# Inverter_v1p0.net
KiCad netlist of a schematic drawn in EAGLE
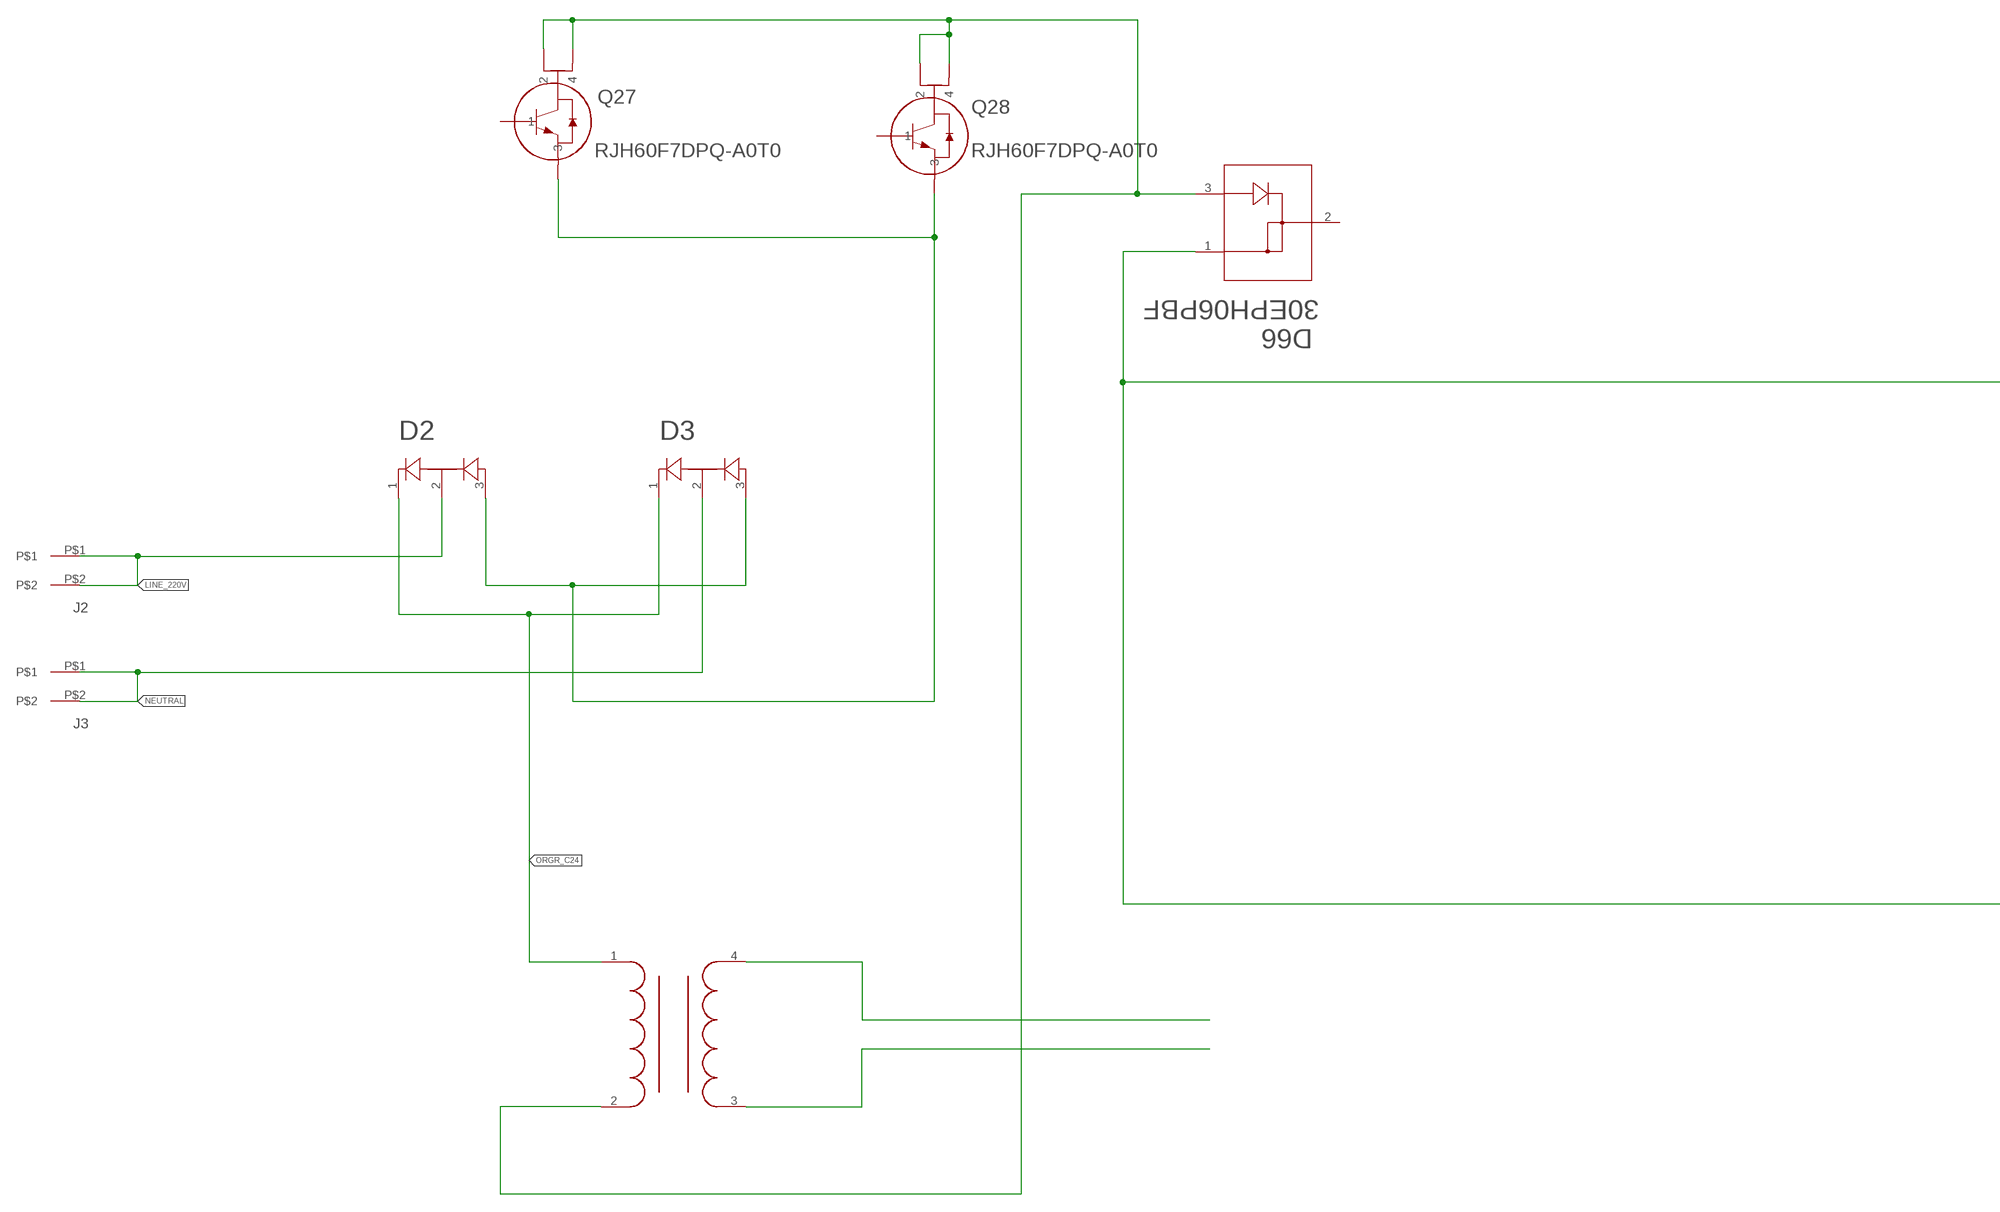
[diagram p0: schematic, sheet 1, part 1 of 2]
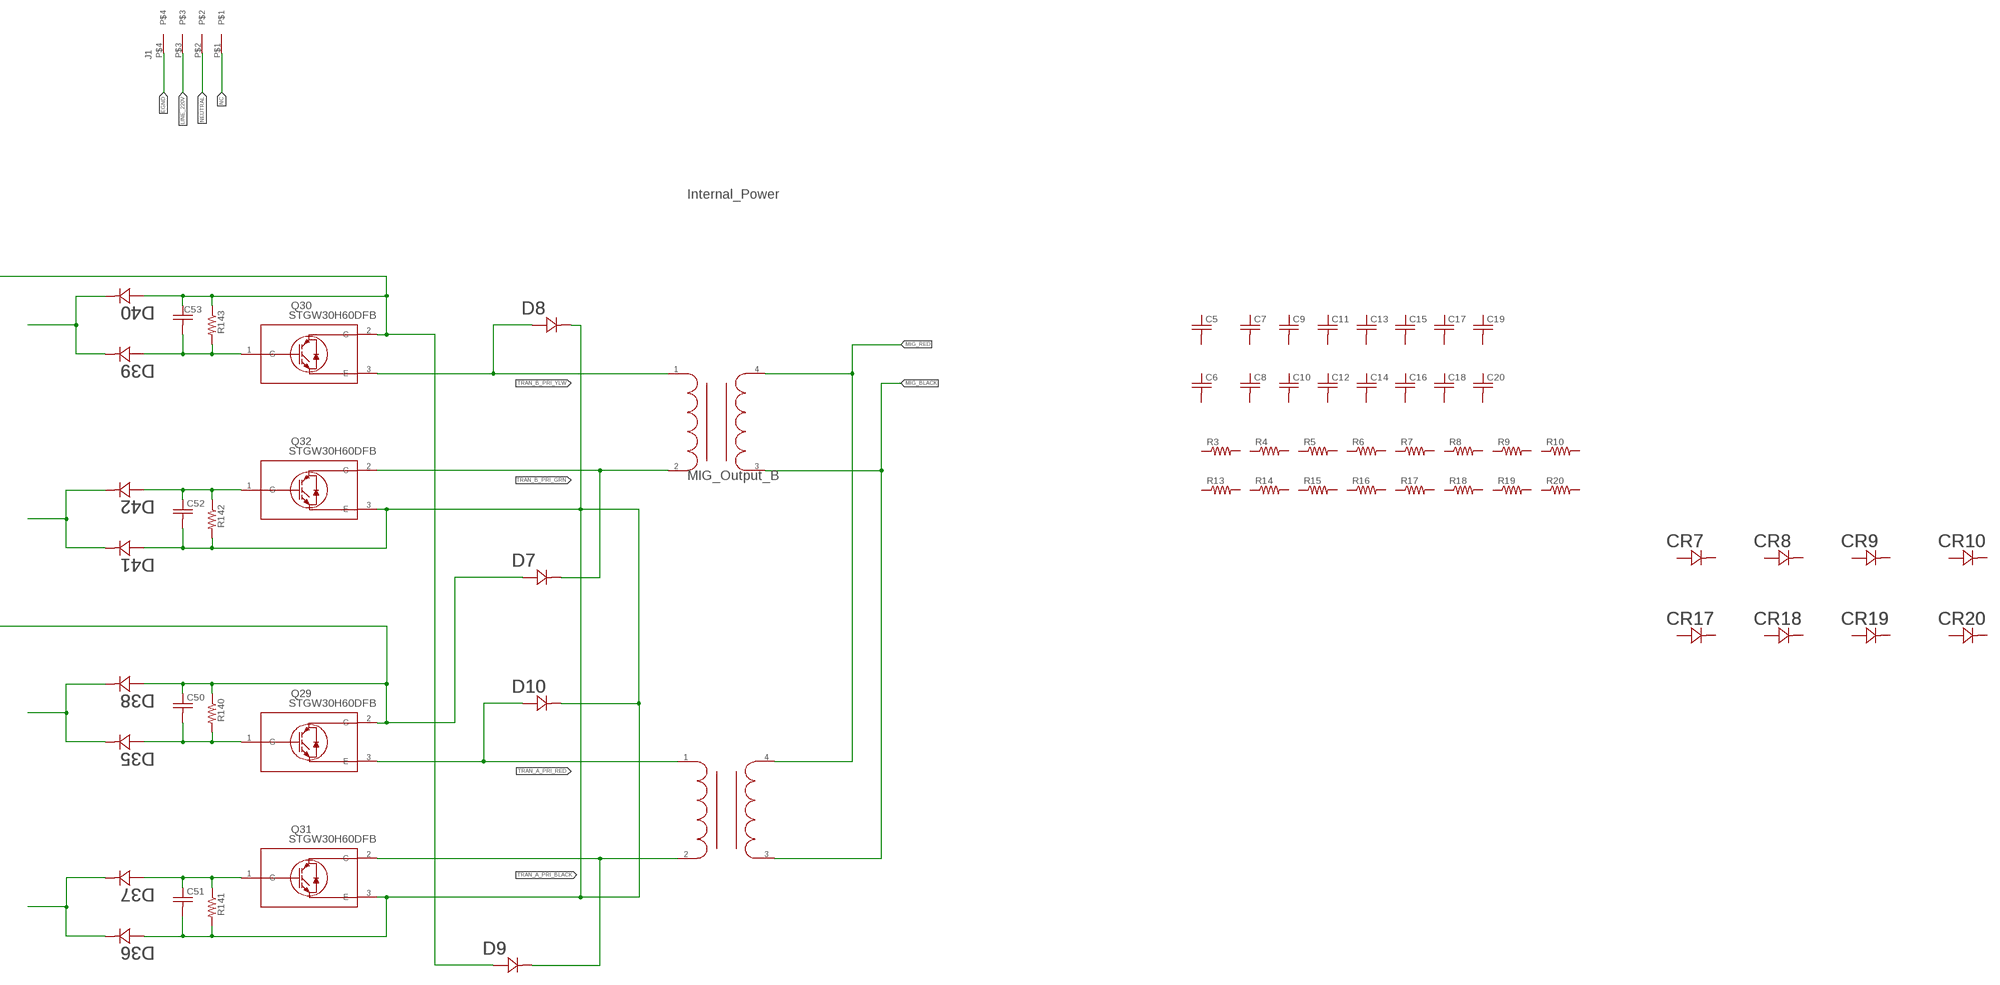
[diagram p1: schematic, sheet 1, part 2 of 2]

(export (version "E")
  (design (tool "Eeschema 10.0.6"))
  (components
    (comp (ref "C5")
      (value "C_0805")
      (footprint "eagle-import:0805")
      (libsource (lib "eagle-import") (part "C_0805"))
    )
    (comp (ref "C6")
      (value "C_0805")
      (footprint "eagle-import:0805")
      (libsource (lib "eagle-import") (part "C_0805"))
    )
    (comp (ref "C7")
      (value "C_0805")
      (footprint "eagle-import:0805")
      (libsource (lib "eagle-import") (part "C_0805"))
    )
    (comp (ref "C8")
      (value "C_0805")
      (footprint "eagle-import:0805")
      (libsource (lib "eagle-import") (part "C_0805"))
    )
    (comp (ref "C9")
      (value "C_0805")
      (footprint "eagle-import:0805")
      (libsource (lib "eagle-import") (part "C_0805"))
    )
    (comp (ref "C10")
      (value "C_0805")
      (footprint "eagle-import:0805")
      (libsource (lib "eagle-import") (part "C_0805"))
    )
    (comp (ref "C11")
      (value "C_0805")
      (footprint "eagle-import:0805")
      (libsource (lib "eagle-import") (part "C_0805"))
    )
    (comp (ref "C12")
      (value "C_0805")
      (footprint "eagle-import:0805")
      (libsource (lib "eagle-import") (part "C_0805"))
    )
    (comp (ref "C13")
      (value "C_0805")
      (footprint "eagle-import:0805")
      (libsource (lib "eagle-import") (part "C_0805"))
    )
    (comp (ref "C14")
      (value "C_0805")
      (footprint "eagle-import:0805")
      (libsource (lib "eagle-import") (part "C_0805"))
    )
    (comp (ref "C15")
      (value "C_0805")
      (footprint "eagle-import:0805")
      (libsource (lib "eagle-import") (part "C_0805"))
    )
    (comp (ref "C16")
      (value "C_0805")
      (footprint "eagle-import:0805")
      (libsource (lib "eagle-import") (part "C_0805"))
    )
    (comp (ref "C17")
      (value "C_0805")
      (footprint "eagle-import:0805")
      (libsource (lib "eagle-import") (part "C_0805"))
    )
    (comp (ref "C18")
      (value "C_0805")
      (footprint "eagle-import:0805")
      (libsource (lib "eagle-import") (part "C_0805"))
    )
    (comp (ref "C19")
      (value "C_0805")
      (footprint "eagle-import:0805")
      (libsource (lib "eagle-import") (part "C_0805"))
    )
    (comp (ref "C20")
      (value "C_0805")
      (footprint "eagle-import:0805")
      (libsource (lib "eagle-import") (part "C_0805"))
    )
    (comp (ref "C50")
      (value "C_0805")
      (footprint "eagle-import:0805")
      (libsource (lib "eagle-import") (part "C_0805"))
    )
    (comp (ref "C51")
      (value "C_0805")
      (footprint "eagle-import:0805")
      (libsource (lib "eagle-import") (part "C_0805"))
    )
    (comp (ref "C52")
      (value "C_0805")
      (footprint "eagle-import:0805")
      (libsource (lib "eagle-import") (part "C_0805"))
    )
    (comp (ref "C53")
      (value "C_0805")
      (footprint "eagle-import:0805")
      (libsource (lib "eagle-import") (part "C_0805"))
    )
    (comp (ref "CR7")
      (value "GF1D-E3")
      (footprint "eagle-import:DO-214BA_VIS")
      (libsource (lib "eagle-import") (part "GF1D-E3"))
    )
    (comp (ref "CR8")
      (value "GF1D-E3")
      (footprint "eagle-import:DO-214BA_VIS")
      (libsource (lib "eagle-import") (part "GF1D-E3"))
    )
    (comp (ref "CR9")
      (value "GF1D-E3")
      (footprint "eagle-import:DO-214BA_VIS")
      (libsource (lib "eagle-import") (part "GF1D-E3"))
    )
    (comp (ref "CR10")
      (value "GF1D-E3")
      (footprint "eagle-import:DO-214BA_VIS")
      (libsource (lib "eagle-import") (part "GF1D-E3"))
    )
    (comp (ref "CR17")
      (value "GF1D-E3")
      (footprint "eagle-import:DO-214BA_VIS")
      (libsource (lib "eagle-import") (part "GF1D-E3"))
    )
    (comp (ref "CR18")
      (value "GF1D-E3")
      (footprint "eagle-import:DO-214BA_VIS")
      (libsource (lib "eagle-import") (part "GF1D-E3"))
    )
    (comp (ref "CR19")
      (value "GF1D-E3")
      (footprint "eagle-import:DO-214BA_VIS")
      (libsource (lib "eagle-import") (part "GF1D-E3"))
    )
    (comp (ref "CR20")
      (value "GF1D-E3")
      (footprint "eagle-import:DO-214BA_VIS")
      (libsource (lib "eagle-import") (part "GF1D-E3"))
    )
    (comp (ref "D2")
      (value "SDD25N12")
      (footprint "eagle-import:TO-247AD")
      (libsource (lib "eagle-import") (part "SDD25N12"))
    )
    (comp (ref "D3")
      (value "SDD25N12")
      (footprint "eagle-import:TO-247AD")
      (libsource (lib "eagle-import") (part "SDD25N12"))
    )
    (comp (ref "D7")
      (value "GF1D-E3")
      (footprint "eagle-import:DO-214BA_VIS")
      (libsource (lib "eagle-import") (part "GF1D-E3"))
    )
    (comp (ref "D8")
      (value "GF1D-E3")
      (footprint "eagle-import:DO-214BA_VIS")
      (libsource (lib "eagle-import") (part "GF1D-E3"))
    )
    (comp (ref "D9")
      (value "GF1D-E3")
      (footprint "eagle-import:DO-214BA_VIS")
      (libsource (lib "eagle-import") (part "GF1D-E3"))
    )
    (comp (ref "D10")
      (value "GF1D-E3")
      (footprint "eagle-import:DO-214BA_VIS")
      (libsource (lib "eagle-import") (part "GF1D-E3"))
    )
    (comp (ref "D35")
      (value "GF1D-E3")
      (footprint "eagle-import:DO-214BA_VIS")
      (libsource (lib "eagle-import") (part "GF1D-E3"))
    )
    (comp (ref "D36")
      (value "GF1D-E3")
      (footprint "eagle-import:DO-214BA_VIS")
      (libsource (lib "eagle-import") (part "GF1D-E3"))
    )
    (comp (ref "D37")
      (value "GF1D-E3")
      (footprint "eagle-import:DO-214BA_VIS")
      (libsource (lib "eagle-import") (part "GF1D-E3"))
    )
    (comp (ref "D38")
      (value "GF1D-E3")
      (footprint "eagle-import:DO-214BA_VIS")
      (libsource (lib "eagle-import") (part "GF1D-E3"))
    )
    (comp (ref "D39")
      (value "GF1D-E3")
      (footprint "eagle-import:DO-214BA_VIS")
      (libsource (lib "eagle-import") (part "GF1D-E3"))
    )
    (comp (ref "D40")
      (value "GF1D-E3")
      (footprint "eagle-import:DO-214BA_VIS")
      (libsource (lib "eagle-import") (part "GF1D-E3"))
    )
    (comp (ref "D41")
      (value "GF1D-E3")
      (footprint "eagle-import:DO-214BA_VIS")
      (libsource (lib "eagle-import") (part "GF1D-E3"))
    )
    (comp (ref "D42")
      (value "GF1D-E3")
      (footprint "eagle-import:DO-214BA_VIS")
      (libsource (lib "eagle-import") (part "GF1D-E3"))
    )
    (comp (ref "D66")
      (value "30EPH06PBF")
      (footprint "eagle-import:TO-247AC_MOD_VIS")
      (libsource (lib "eagle-import") (part "30EPH06PBF"))
    )
    (comp (ref "J1")
      (value "4-pos")
      (footprint "eagle-import:1X4_3.81MM_PITCH")
      (fields (field (name "PARTNO") "691322310004"))
      (libsource (lib "eagle-import") (part "3.81MM_1_X_4_RT_ANGLE_PLUG_HEADER"))
    )
    (comp (ref "J2")
      (value "2-pos")
      (footprint "eagle-import:2_3.81MM_PITCH")
      (fields (field (name "PARTNO") "691322310002"))
      (libsource (lib "eagle-import") (part "3.81MM_1_X_2_RT_ANGLE_PLUG_HEADER"))
    )
    (comp (ref "J3")
      (value "2-pos")
      (footprint "eagle-import:2_3.81MM_PITCH")
      (fields (field (name "PARTNO") "691322310002"))
      (libsource (lib "eagle-import") (part "3.81MM_1_X_2_RT_ANGLE_PLUG_HEADER"))
    )
    (comp (ref "Q27")
      (value "RJH60F7DPQ-A0T0")
      (footprint "eagle-import:TO-247A_REN")
      (fields (field (name "MANUFACTURER_PART_NUMBER") "RJH60F7DPQ-A0#T0"))
      (libsource (lib "eagle-import") (part "RJH60F7DPQ-A0T0"))
    )
    (comp (ref "Q28")
      (value "RJH60F7DPQ-A0T0")
      (footprint "eagle-import:TO-247A_REN")
      (fields (field (name "MANUFACTURER_PART_NUMBER") "RJH60F7DPQ-A0#T0"))
      (libsource (lib "eagle-import") (part "RJH60F7DPQ-A0T0"))
    )
    (comp (ref "Q29")
      (value "STGW30H60DFB")
      (footprint "eagle-import:TO-247_STM")
      (fields (field (name "COPYRIGHT") "Copyright (C) 2018 Accelerated Designs. All rights reserved"))
      (libsource (lib "eagle-import") (part "STGW30H60DFB"))
    )
    (comp (ref "Q30")
      (value "STGW30H60DFB")
      (footprint "eagle-import:TO-247_STM")
      (fields (field (name "COPYRIGHT") "Copyright (C) 2018 Accelerated Designs. All rights reserved"))
      (libsource (lib "eagle-import") (part "STGW30H60DFB"))
    )
    (comp (ref "Q31")
      (value "STGW30H60DFB")
      (footprint "eagle-import:TO-247_STM")
      (fields (field (name "COPYRIGHT") "Copyright (C) 2018 Accelerated Designs. All rights reserved"))
      (libsource (lib "eagle-import") (part "STGW30H60DFB"))
    )
    (comp (ref "Q32")
      (value "STGW30H60DFB")
      (footprint "eagle-import:TO-247_STM")
      (fields (field (name "COPYRIGHT") "Copyright (C) 2018 Accelerated Designs. All rights reserved"))
      (libsource (lib "eagle-import") (part "STGW30H60DFB"))
    )
    (comp (ref "R3")
      (value "R_0805")
      (footprint "eagle-import:0805")
      (libsource (lib "eagle-import") (part "R_0805"))
    )
    (comp (ref "R4")
      (value "R_0805")
      (footprint "eagle-import:0805")
      (libsource (lib "eagle-import") (part "R_0805"))
    )
    (comp (ref "R5")
      (value "R_0805")
      (footprint "eagle-import:0805")
      (libsource (lib "eagle-import") (part "R_0805"))
    )
    (comp (ref "R6")
      (value "R_0805")
      (footprint "eagle-import:0805")
      (libsource (lib "eagle-import") (part "R_0805"))
    )
    (comp (ref "R7")
      (value "R_0805")
      (footprint "eagle-import:0805")
      (libsource (lib "eagle-import") (part "R_0805"))
    )
    (comp (ref "R8")
      (value "R_0805")
      (footprint "eagle-import:0805")
      (libsource (lib "eagle-import") (part "R_0805"))
    )
    (comp (ref "R9")
      (value "R_0805")
      (footprint "eagle-import:0805")
      (libsource (lib "eagle-import") (part "R_0805"))
    )
    (comp (ref "R10")
      (value "R_0805")
      (footprint "eagle-import:0805")
      (libsource (lib "eagle-import") (part "R_0805"))
    )
    (comp (ref "R13")
      (value "R_0805")
      (footprint "eagle-import:0805")
      (libsource (lib "eagle-import") (part "R_0805"))
    )
    (comp (ref "R14")
      (value "R_0805")
      (footprint "eagle-import:0805")
      (libsource (lib "eagle-import") (part "R_0805"))
    )
    (comp (ref "R15")
      (value "R_0805")
      (footprint "eagle-import:0805")
      (libsource (lib "eagle-import") (part "R_0805"))
    )
    (comp (ref "R16")
      (value "R_0805")
      (footprint "eagle-import:0805")
      (libsource (lib "eagle-import") (part "R_0805"))
    )
    (comp (ref "R17")
      (value "R_0805")
      (footprint "eagle-import:0805")
      (libsource (lib "eagle-import") (part "R_0805"))
    )
    (comp (ref "R18")
      (value "R_0805")
      (footprint "eagle-import:0805")
      (libsource (lib "eagle-import") (part "R_0805"))
    )
    (comp (ref "R19")
      (value "R_0805")
      (footprint "eagle-import:0805")
      (libsource (lib "eagle-import") (part "R_0805"))
    )
    (comp (ref "R20")
      (value "R_0805")
      (footprint "eagle-import:0805")
      (libsource (lib "eagle-import") (part "R_0805"))
    )
    (comp (ref "R140")
      (value "R_0805")
      (footprint "eagle-import:0805")
      (libsource (lib "eagle-import") (part "R_0805"))
    )
    (comp (ref "R141")
      (value "R_0805")
      (footprint "eagle-import:0805")
      (libsource (lib "eagle-import") (part "R_0805"))
    )
    (comp (ref "R142")
      (value "R_0805")
      (footprint "eagle-import:0805")
      (libsource (lib "eagle-import") (part "R_0805"))
    )
    (comp (ref "R143")
      (value "R_0805")
      (footprint "eagle-import:0805")
      (libsource (lib "eagle-import") (part "R_0805"))
    )
    (comp (ref "U$1")
      (value "GENERIC_TRANSFORMER")
      (footprint "eagle-import:GENERIC_TRANSFORMER")
      (libsource (lib "eagle-import") (part "GENERIC_TRANSFORMER"))
    )
    (comp (ref "U$2")
      (value "GENERIC_TRANSFORMER")
      (footprint "eagle-import:GENERIC_TRANSFORMER")
      (libsource (lib "eagle-import") (part "GENERIC_TRANSFORMER"))
    )
    (comp (ref "U$3")
      (value "GENERIC_TRANSFORMER")
      (footprint "eagle-import:GENERIC_TRANSFORMER")
      (libsource (lib "eagle-import") (part "GENERIC_TRANSFORMER"))
    )
  )
  (nets
    (net (code "1") (name "EGND") (class "Default")
      (node (ref "J1") (pin "P$4") (pinfunction "P$4_P$4") (pintype "bidirectional"))
    )
    (net (code "2") (name "LINE_220V") (class "Default")
      (node (ref "D2") (pin "2") (pinfunction "2_2") (pintype "passive"))
      (node (ref "J1") (pin "P$3") (pinfunction "P$3_P$3") (pintype "bidirectional"))
      (node (ref "J2") (pin "P$1") (pinfunction "P$1_P$1") (pintype "bidirectional"))
      (node (ref "J2") (pin "P$2") (pinfunction "P$2_P$2") (pintype "bidirectional"))
    )
    (net (code "3") (name "MIG_BLACK") (class "Default")
      (node (ref "U$1") (pin "3") (pinfunction "3_3") (pintype "passive"))
      (node (ref "U$2") (pin "3") (pinfunction "3_3") (pintype "passive"))
    )
    (net (code "4") (name "MIG_RED") (class "Default")
      (node (ref "U$1") (pin "4") (pinfunction "4_4") (pintype "passive"))
      (node (ref "U$2") (pin "4") (pinfunction "4_4") (pintype "passive"))
    )
    (net (code "5") (name "NC") (class "Default")
      (node (ref "J1") (pin "P$1") (pinfunction "P$1_P$1") (pintype "bidirectional"))
    )
    (net (code "6") (name "NEUTRAL") (class "Default")
      (node (ref "D3") (pin "2") (pinfunction "2_2") (pintype "passive"))
      (node (ref "J1") (pin "P$2") (pinfunction "P$2_P$2") (pintype "bidirectional"))
      (node (ref "J3") (pin "P$1") (pinfunction "P$1_P$1") (pintype "bidirectional"))
      (node (ref "J3") (pin "P$2") (pinfunction "P$2_P$2") (pintype "bidirectional"))
    )
    (net (code "7") (name "Net-(D2-Pad3)") (class "Default")
      (node (ref "D2") (pin "3") (pinfunction "3_3") (pintype "passive"))
      (node (ref "D3") (pin "3") (pinfunction "3_3") (pintype "passive"))
      (node (ref "Q27") (pin "3") (pinfunction "3_3") (pintype "passive"))
      (node (ref "Q28") (pin "3") (pinfunction "3_3") (pintype "passive"))
    )
    (net (code "8") (name "Net-(D35-Pad1)") (class "Default")
      (node (ref "D35") (pin "1") (pinfunction "1_1") (pintype "passive"))
      (node (ref "D38") (pin "1") (pinfunction "1_1") (pintype "passive"))
    )
    (net (code "9") (name "Net-(D36-Pad1)") (class "Default")
      (node (ref "D36") (pin "1") (pinfunction "1_1") (pintype "passive"))
      (node (ref "D37") (pin "1") (pinfunction "1_1") (pintype "passive"))
    )
    (net (code "10") (name "Net-(D39-Pad1)") (class "Default")
      (node (ref "D39") (pin "1") (pinfunction "1_1") (pintype "passive"))
      (node (ref "D40") (pin "1") (pinfunction "1_1") (pintype "passive"))
    )
    (net (code "11") (name "Net-(D41-Pad1)") (class "Default")
      (node (ref "D41") (pin "1") (pinfunction "1_1") (pintype "passive"))
      (node (ref "D42") (pin "1") (pinfunction "1_1") (pintype "passive"))
    )
    (net (code "12") (name "Net-(D66-Pad3)") (class "Default")
      (node (ref "D66") (pin "3") (pinfunction "3_3") (pintype "passive"))
      (node (ref "Q27") (pin "2") (pinfunction "2_2") (pintype "passive"))
      (node (ref "Q27") (pin "4") (pinfunction "4_4") (pintype "passive"))
      (node (ref "Q28") (pin "2") (pinfunction "2_2") (pintype "passive"))
      (node (ref "Q28") (pin "4") (pinfunction "4_4") (pintype "passive"))
      (node (ref "U$3") (pin "2") (pinfunction "2_2") (pintype "passive"))
    )
    (net (code "13") (name "Net-(Q29-C)") (class "Default")
      (node (ref "C50") (pin "1") (pinfunction "1_1") (pintype "passive"))
      (node (ref "C53") (pin "1") (pinfunction "1_1") (pintype "passive"))
      (node (ref "D38") (pin "2") (pinfunction "2_2") (pintype "passive"))
      (node (ref "D40") (pin "2") (pinfunction "2_2") (pintype "passive"))
      (node (ref "D66") (pin "1") (pinfunction "1_1") (pintype "passive"))
      (node (ref "D7") (pin "2") (pinfunction "2_2") (pintype "passive"))
      (node (ref "D9") (pin "2") (pinfunction "2_2") (pintype "passive"))
      (node (ref "Q29") (pin "2") (pinfunction "C_2") (pintype "passive"))
      (node (ref "Q30") (pin "2") (pinfunction "C_2") (pintype "passive"))
      (node (ref "R140") (pin "1") (pinfunction "1_1") (pintype "passive"))
      (node (ref "R143") (pin "1") (pinfunction "1_1") (pintype "passive"))
    )
    (net (code "14") (name "Net-(Q29-G)") (class "Default")
      (node (ref "C50") (pin "2") (pinfunction "2_2") (pintype "passive"))
      (node (ref "D35") (pin "2") (pinfunction "2_2") (pintype "passive"))
      (node (ref "Q29") (pin "1") (pinfunction "G_1") (pintype "passive"))
      (node (ref "R140") (pin "2") (pinfunction "2_2") (pintype "passive"))
    )
    (net (code "15") (name "Net-(Q30-G)") (class "Default")
      (node (ref "C53") (pin "2") (pinfunction "2_2") (pintype "passive"))
      (node (ref "D39") (pin "2") (pinfunction "2_2") (pintype "passive"))
      (node (ref "Q30") (pin "1") (pinfunction "G_1") (pintype "passive"))
      (node (ref "R143") (pin "2") (pinfunction "2_2") (pintype "passive"))
    )
    (net (code "16") (name "Net-(Q31-E)") (class "Default")
      (node (ref "C51") (pin "2") (pinfunction "2_2") (pintype "passive"))
      (node (ref "C52") (pin "2") (pinfunction "2_2") (pintype "passive"))
      (node (ref "D10") (pin "1") (pinfunction "1_1") (pintype "passive"))
      (node (ref "D36") (pin "2") (pinfunction "2_2") (pintype "passive"))
      (node (ref "D41") (pin "2") (pinfunction "2_2") (pintype "passive"))
      (node (ref "D8") (pin "1") (pinfunction "1_1") (pintype "passive"))
      (node (ref "Q31") (pin "3") (pinfunction "E_3") (pintype "passive"))
      (node (ref "Q32") (pin "3") (pinfunction "E_3") (pintype "passive"))
      (node (ref "R141") (pin "2") (pinfunction "2_2") (pintype "passive"))
      (node (ref "R142") (pin "2") (pinfunction "2_2") (pintype "passive"))
    )
    (net (code "17") (name "Net-(Q31-G)") (class "Default")
      (node (ref "C51") (pin "1") (pinfunction "1_1") (pintype "passive"))
      (node (ref "D37") (pin "2") (pinfunction "2_2") (pintype "passive"))
      (node (ref "Q31") (pin "1") (pinfunction "G_1") (pintype "passive"))
      (node (ref "R141") (pin "1") (pinfunction "1_1") (pintype "passive"))
    )
    (net (code "18") (name "Net-(Q32-G)") (class "Default")
      (node (ref "C52") (pin "1") (pinfunction "1_1") (pintype "passive"))
      (node (ref "D42") (pin "2") (pinfunction "2_2") (pintype "passive"))
      (node (ref "Q32") (pin "1") (pinfunction "G_1") (pintype "passive"))
      (node (ref "R142") (pin "1") (pinfunction "1_1") (pintype "passive"))
    )
    (net (code "19") (name "ORGR_C24") (class "Default")
      (node (ref "D2") (pin "1") (pinfunction "1_1") (pintype "passive"))
      (node (ref "D3") (pin "1") (pinfunction "1_1") (pintype "passive"))
      (node (ref "U$3") (pin "1") (pinfunction "1_1") (pintype "passive"))
    )
    (net (code "20") (name "TRAN_A_PRI_BLACK") (class "Default")
      (node (ref "D9") (pin "1") (pinfunction "1_1") (pintype "passive"))
      (node (ref "Q31") (pin "2") (pinfunction "C_2") (pintype "passive"))
      (node (ref "U$2") (pin "2") (pinfunction "2_2") (pintype "passive"))
    )
    (net (code "21") (name "TRAN_A_PRI_RED") (class "Default")
      (node (ref "D10") (pin "2") (pinfunction "2_2") (pintype "passive"))
      (node (ref "Q29") (pin "3") (pinfunction "E_3") (pintype "passive"))
      (node (ref "U$2") (pin "1") (pinfunction "1_1") (pintype "passive"))
    )
    (net (code "22") (name "TRAN_B_PRI_GRN") (class "Default")
      (node (ref "D7") (pin "1") (pinfunction "1_1") (pintype "passive"))
      (node (ref "Q32") (pin "2") (pinfunction "C_2") (pintype "passive"))
      (node (ref "U$1") (pin "2") (pinfunction "2_2") (pintype "passive"))
    )
    (net (code "23") (name "TRAN_B_PRI_YLW") (class "Default")
      (node (ref "D8") (pin "2") (pinfunction "2_2") (pintype "passive"))
      (node (ref "Q30") (pin "3") (pinfunction "E_3") (pintype "passive"))
      (node (ref "U$1") (pin "1") (pinfunction "1_1") (pintype "passive"))
    )
    (net (code "24") (name "unconnected-(C5-Pad1)") (class "Default")
      (node (ref "C5") (pin "1") (pinfunction "1_1") (pintype "passive"))
    )
    (net (code "25") (name "unconnected-(C5-Pad2)") (class "Default")
      (node (ref "C5") (pin "2") (pinfunction "2_2") (pintype "passive"))
    )
    (net (code "26") (name "unconnected-(C6-Pad1)") (class "Default")
      (node (ref "C6") (pin "1") (pinfunction "1_1") (pintype "passive"))
    )
    (net (code "27") (name "unconnected-(C6-Pad2)") (class "Default")
      (node (ref "C6") (pin "2") (pinfunction "2_2") (pintype "passive"))
    )
    (net (code "28") (name "unconnected-(C7-Pad1)") (class "Default")
      (node (ref "C7") (pin "1") (pinfunction "1_1") (pintype "passive"))
    )
    (net (code "29") (name "unconnected-(C7-Pad2)") (class "Default")
      (node (ref "C7") (pin "2") (pinfunction "2_2") (pintype "passive"))
    )
    (net (code "30") (name "unconnected-(C8-Pad1)") (class "Default")
      (node (ref "C8") (pin "1") (pinfunction "1_1") (pintype "passive"))
    )
    (net (code "31") (name "unconnected-(C8-Pad2)") (class "Default")
      (node (ref "C8") (pin "2") (pinfunction "2_2") (pintype "passive"))
    )
    (net (code "32") (name "unconnected-(C9-Pad1)") (class "Default")
      (node (ref "C9") (pin "1") (pinfunction "1_1") (pintype "passive"))
    )
    (net (code "33") (name "unconnected-(C9-Pad2)") (class "Default")
      (node (ref "C9") (pin "2") (pinfunction "2_2") (pintype "passive"))
    )
    (net (code "34") (name "unconnected-(C10-Pad1)") (class "Default")
      (node (ref "C10") (pin "1") (pinfunction "1_1") (pintype "passive"))
    )
    (net (code "35") (name "unconnected-(C10-Pad2)") (class "Default")
      (node (ref "C10") (pin "2") (pinfunction "2_2") (pintype "passive"))
    )
    (net (code "36") (name "unconnected-(C11-Pad1)") (class "Default")
      (node (ref "C11") (pin "1") (pinfunction "1_1") (pintype "passive"))
    )
    (net (code "37") (name "unconnected-(C11-Pad2)") (class "Default")
      (node (ref "C11") (pin "2") (pinfunction "2_2") (pintype "passive"))
    )
    (net (code "38") (name "unconnected-(C12-Pad1)") (class "Default")
      (node (ref "C12") (pin "1") (pinfunction "1_1") (pintype "passive"))
    )
    (net (code "39") (name "unconnected-(C12-Pad2)") (class "Default")
      (node (ref "C12") (pin "2") (pinfunction "2_2") (pintype "passive"))
    )
    (net (code "40") (name "unconnected-(C13-Pad1)") (class "Default")
      (node (ref "C13") (pin "1") (pinfunction "1_1") (pintype "passive"))
    )
    (net (code "41") (name "unconnected-(C13-Pad2)") (class "Default")
      (node (ref "C13") (pin "2") (pinfunction "2_2") (pintype "passive"))
    )
    (net (code "42") (name "unconnected-(C14-Pad1)") (class "Default")
      (node (ref "C14") (pin "1") (pinfunction "1_1") (pintype "passive"))
    )
    (net (code "43") (name "unconnected-(C14-Pad2)") (class "Default")
      (node (ref "C14") (pin "2") (pinfunction "2_2") (pintype "passive"))
    )
    (net (code "44") (name "unconnected-(C15-Pad1)") (class "Default")
      (node (ref "C15") (pin "1") (pinfunction "1_1") (pintype "passive"))
    )
    (net (code "45") (name "unconnected-(C15-Pad2)") (class "Default")
      (node (ref "C15") (pin "2") (pinfunction "2_2") (pintype "passive"))
    )
    (net (code "46") (name "unconnected-(C16-Pad1)") (class "Default")
      (node (ref "C16") (pin "1") (pinfunction "1_1") (pintype "passive"))
    )
    (net (code "47") (name "unconnected-(C16-Pad2)") (class "Default")
      (node (ref "C16") (pin "2") (pinfunction "2_2") (pintype "passive"))
    )
    (net (code "48") (name "unconnected-(C17-Pad1)") (class "Default")
      (node (ref "C17") (pin "1") (pinfunction "1_1") (pintype "passive"))
    )
    (net (code "49") (name "unconnected-(C17-Pad2)") (class "Default")
      (node (ref "C17") (pin "2") (pinfunction "2_2") (pintype "passive"))
    )
    (net (code "50") (name "unconnected-(C18-Pad1)") (class "Default")
      (node (ref "C18") (pin "1") (pinfunction "1_1") (pintype "passive"))
    )
    (net (code "51") (name "unconnected-(C18-Pad2)") (class "Default")
      (node (ref "C18") (pin "2") (pinfunction "2_2") (pintype "passive"))
    )
    (net (code "52") (name "unconnected-(C19-Pad1)") (class "Default")
      (node (ref "C19") (pin "1") (pinfunction "1_1") (pintype "passive"))
    )
    (net (code "53") (name "unconnected-(C19-Pad2)") (class "Default")
      (node (ref "C19") (pin "2") (pinfunction "2_2") (pintype "passive"))
    )
    (net (code "54") (name "unconnected-(C20-Pad1)") (class "Default")
      (node (ref "C20") (pin "1") (pinfunction "1_1") (pintype "passive"))
    )
    (net (code "55") (name "unconnected-(C20-Pad2)") (class "Default")
      (node (ref "C20") (pin "2") (pinfunction "2_2") (pintype "passive"))
    )
    (net (code "56") (name "unconnected-(CR7-Pad1)") (class "Default")
      (node (ref "CR7") (pin "1") (pinfunction "1_1") (pintype "passive"))
    )
    (net (code "57") (name "unconnected-(CR7-Pad2)") (class "Default")
      (node (ref "CR7") (pin "2") (pinfunction "2_2") (pintype "passive"))
    )
    (net (code "58") (name "unconnected-(CR8-Pad1)") (class "Default")
      (node (ref "CR8") (pin "1") (pinfunction "1_1") (pintype "passive"))
    )
    (net (code "59") (name "unconnected-(CR8-Pad2)") (class "Default")
      (node (ref "CR8") (pin "2") (pinfunction "2_2") (pintype "passive"))
    )
    (net (code "60") (name "unconnected-(CR9-Pad1)") (class "Default")
      (node (ref "CR9") (pin "1") (pinfunction "1_1") (pintype "passive"))
    )
    (net (code "61") (name "unconnected-(CR9-Pad2)") (class "Default")
      (node (ref "CR9") (pin "2") (pinfunction "2_2") (pintype "passive"))
    )
    (net (code "62") (name "unconnected-(CR10-Pad1)") (class "Default")
      (node (ref "CR10") (pin "1") (pinfunction "1_1") (pintype "passive"))
    )
    (net (code "63") (name "unconnected-(CR10-Pad2)") (class "Default")
      (node (ref "CR10") (pin "2") (pinfunction "2_2") (pintype "passive"))
    )
    (net (code "64") (name "unconnected-(CR17-Pad1)") (class "Default")
      (node (ref "CR17") (pin "1") (pinfunction "1_1") (pintype "passive"))
    )
    (net (code "65") (name "unconnected-(CR17-Pad2)") (class "Default")
      (node (ref "CR17") (pin "2") (pinfunction "2_2") (pintype "passive"))
    )
    (net (code "66") (name "unconnected-(CR18-Pad1)") (class "Default")
      (node (ref "CR18") (pin "1") (pinfunction "1_1") (pintype "passive"))
    )
    (net (code "67") (name "unconnected-(CR18-Pad2)") (class "Default")
      (node (ref "CR18") (pin "2") (pinfunction "2_2") (pintype "passive"))
    )
    (net (code "68") (name "unconnected-(CR19-Pad1)") (class "Default")
      (node (ref "CR19") (pin "1") (pinfunction "1_1") (pintype "passive"))
    )
    (net (code "69") (name "unconnected-(CR19-Pad2)") (class "Default")
      (node (ref "CR19") (pin "2") (pinfunction "2_2") (pintype "passive"))
    )
    (net (code "70") (name "unconnected-(CR20-Pad1)") (class "Default")
      (node (ref "CR20") (pin "1") (pinfunction "1_1") (pintype "passive"))
    )
    (net (code "71") (name "unconnected-(CR20-Pad2)") (class "Default")
      (node (ref "CR20") (pin "2") (pinfunction "2_2") (pintype "passive"))
    )
    (net (code "72") (name "unconnected-(D66-Pad2)") (class "Default")
      (node (ref "D66") (pin "2") (pinfunction "2_2") (pintype "passive"))
    )
    (net (code "73") (name "unconnected-(Q27-Pad1)") (class "Default")
      (node (ref "Q27") (pin "1") (pinfunction "1_1") (pintype "passive"))
    )
    (net (code "74") (name "unconnected-(Q28-Pad1)") (class "Default")
      (node (ref "Q28") (pin "1") (pinfunction "1_1") (pintype "passive"))
    )
    (net (code "75") (name "unconnected-(R3-Pad1)") (class "Default")
      (node (ref "R3") (pin "1") (pinfunction "1_1") (pintype "passive"))
    )
    (net (code "76") (name "unconnected-(R3-Pad2)") (class "Default")
      (node (ref "R3") (pin "2") (pinfunction "2_2") (pintype "passive"))
    )
    (net (code "77") (name "unconnected-(R4-Pad1)") (class "Default")
      (node (ref "R4") (pin "1") (pinfunction "1_1") (pintype "passive"))
    )
    (net (code "78") (name "unconnected-(R4-Pad2)") (class "Default")
      (node (ref "R4") (pin "2") (pinfunction "2_2") (pintype "passive"))
    )
    (net (code "79") (name "unconnected-(R5-Pad1)") (class "Default")
      (node (ref "R5") (pin "1") (pinfunction "1_1") (pintype "passive"))
    )
    (net (code "80") (name "unconnected-(R5-Pad2)") (class "Default")
      (node (ref "R5") (pin "2") (pinfunction "2_2") (pintype "passive"))
    )
    (net (code "81") (name "unconnected-(R6-Pad1)") (class "Default")
      (node (ref "R6") (pin "1") (pinfunction "1_1") (pintype "passive"))
    )
    (net (code "82") (name "unconnected-(R6-Pad2)") (class "Default")
      (node (ref "R6") (pin "2") (pinfunction "2_2") (pintype "passive"))
    )
    (net (code "83") (name "unconnected-(R7-Pad1)") (class "Default")
      (node (ref "R7") (pin "1") (pinfunction "1_1") (pintype "passive"))
    )
    (net (code "84") (name "unconnected-(R7-Pad2)") (class "Default")
      (node (ref "R7") (pin "2") (pinfunction "2_2") (pintype "passive"))
    )
    (net (code "85") (name "unconnected-(R8-Pad1)") (class "Default")
      (node (ref "R8") (pin "1") (pinfunction "1_1") (pintype "passive"))
    )
    (net (code "86") (name "unconnected-(R8-Pad2)") (class "Default")
      (node (ref "R8") (pin "2") (pinfunction "2_2") (pintype "passive"))
    )
    (net (code "87") (name "unconnected-(R9-Pad1)") (class "Default")
      (node (ref "R9") (pin "1") (pinfunction "1_1") (pintype "passive"))
    )
    (net (code "88") (name "unconnected-(R9-Pad2)") (class "Default")
      (node (ref "R9") (pin "2") (pinfunction "2_2") (pintype "passive"))
    )
    (net (code "89") (name "unconnected-(R10-Pad1)") (class "Default")
      (node (ref "R10") (pin "1") (pinfunction "1_1") (pintype "passive"))
    )
    (net (code "90") (name "unconnected-(R10-Pad2)") (class "Default")
      (node (ref "R10") (pin "2") (pinfunction "2_2") (pintype "passive"))
    )
    (net (code "91") (name "unconnected-(R13-Pad1)") (class "Default")
      (node (ref "R13") (pin "1") (pinfunction "1_1") (pintype "passive"))
    )
    (net (code "92") (name "unconnected-(R13-Pad2)") (class "Default")
      (node (ref "R13") (pin "2") (pinfunction "2_2") (pintype "passive"))
    )
    (net (code "93") (name "unconnected-(R14-Pad1)") (class "Default")
      (node (ref "R14") (pin "1") (pinfunction "1_1") (pintype "passive"))
    )
    (net (code "94") (name "unconnected-(R14-Pad2)") (class "Default")
      (node (ref "R14") (pin "2") (pinfunction "2_2") (pintype "passive"))
    )
    (net (code "95") (name "unconnected-(R15-Pad1)") (class "Default")
      (node (ref "R15") (pin "1") (pinfunction "1_1") (pintype "passive"))
    )
    (net (code "96") (name "unconnected-(R15-Pad2)") (class "Default")
      (node (ref "R15") (pin "2") (pinfunction "2_2") (pintype "passive"))
    )
    (net (code "97") (name "unconnected-(R16-Pad1)") (class "Default")
      (node (ref "R16") (pin "1") (pinfunction "1_1") (pintype "passive"))
    )
    (net (code "98") (name "unconnected-(R16-Pad2)") (class "Default")
      (node (ref "R16") (pin "2") (pinfunction "2_2") (pintype "passive"))
    )
    (net (code "99") (name "unconnected-(R17-Pad1)") (class "Default")
      (node (ref "R17") (pin "1") (pinfunction "1_1") (pintype "passive"))
    )
    (net (code "100") (name "unconnected-(R17-Pad2)") (class "Default")
      (node (ref "R17") (pin "2") (pinfunction "2_2") (pintype "passive"))
    )
    (net (code "101") (name "unconnected-(R18-Pad1)") (class "Default")
      (node (ref "R18") (pin "1") (pinfunction "1_1") (pintype "passive"))
    )
    (net (code "102") (name "unconnected-(R18-Pad2)") (class "Default")
      (node (ref "R18") (pin "2") (pinfunction "2_2") (pintype "passive"))
    )
    (net (code "103") (name "unconnected-(R19-Pad1)") (class "Default")
      (node (ref "R19") (pin "1") (pinfunction "1_1") (pintype "passive"))
    )
    (net (code "104") (name "unconnected-(R19-Pad2)") (class "Default")
      (node (ref "R19") (pin "2") (pinfunction "2_2") (pintype "passive"))
    )
    (net (code "105") (name "unconnected-(R20-Pad1)") (class "Default")
      (node (ref "R20") (pin "1") (pinfunction "1_1") (pintype "passive"))
    )
    (net (code "106") (name "unconnected-(R20-Pad2)") (class "Default")
      (node (ref "R20") (pin "2") (pinfunction "2_2") (pintype "passive"))
    )
    (net (code "107") (name "unconnected-(U$3-Pad3)") (class "Default")
      (node (ref "U$3") (pin "3") (pinfunction "3_3") (pintype "passive"))
    )
    (net (code "108") (name "unconnected-(U$3-Pad4)") (class "Default")
      (node (ref "U$3") (pin "4") (pinfunction "4_4") (pintype "passive"))
    )
  )
)
